# MCU.net
KiCad netlist of a schematic drawn in Altium Designer
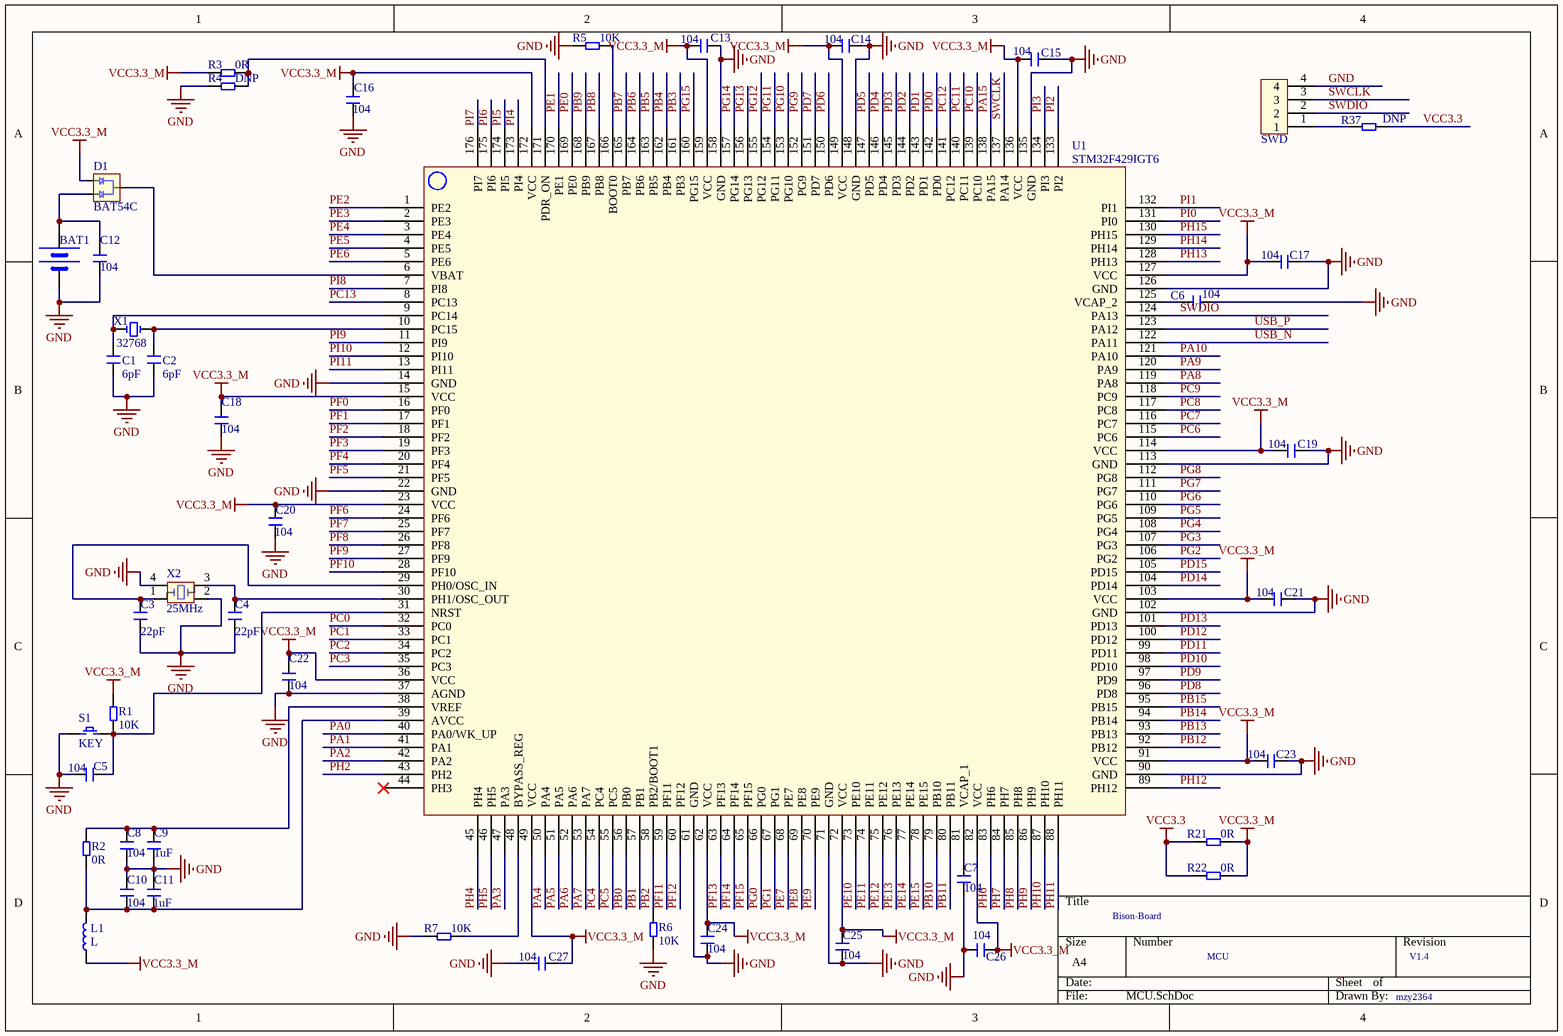
[diagram p0: MCU.SchDoc]

(export (version "E")
  (design (tool "Eeschema 10.0.6"))
  (components
    (comp (ref "BAT1")
      (value "BATTERY")
      (footprint "SBAT-1220")
      (libsource (lib "Bison-Board") (part "BATTERY"))
    )
    (comp (ref "C1") (value "6pF") (footprint "C 0603") (libsource (lib "Bison-Board") (part "CAP")))
    (comp (ref "C2")
      (value "6pF")
      (footprint "C 0603")
      (libsource (lib "altium-import") (part "root_1_CAP_"))
    )
    (comp (ref "C3") (value "22pF") (footprint "C 0603") (libsource (lib "Bison-Board") (part "CAP")))
    (comp (ref "C4") (value "22pF") (footprint "C 0603") (libsource (lib "Bison-Board") (part "CAP")))
    (comp (ref "C5") (value "104") (footprint "C 0603") (libsource (lib "Bison-Board") (part "CAP")))
    (comp (ref "C6") (value "104") (footprint "C 0603") (libsource (lib "Bison-Board") (part "CAP")))
    (comp (ref "C7") (value "104") (footprint "C 0603") (libsource (lib "Bison-Board") (part "CAP")))
    (comp (ref "C8") (value "104") (footprint "C 0603") (libsource (lib "Bison-Board") (part "CAP")))
    (comp (ref "C9") (value "1uF") (footprint "C 0603") (libsource (lib "Bison-Board") (part "CAP")))
    (comp (ref "C10") (value "104") (footprint "C 0603") (libsource (lib "Bison-Board") (part "CAP")))
    (comp (ref "C11") (value "1uF") (footprint "C 0603") (libsource (lib "Bison-Board") (part "CAP")))
    (comp (ref "C12") (value "104") (footprint "C 0603") (libsource (lib "Bison-Board") (part "CAP")))
    (comp (ref "C13") (value "104") (footprint "C 0603") (libsource (lib "Bison-Board") (part "CAP")))
    (comp (ref "C14") (value "104") (footprint "C 0603") (libsource (lib "Bison-Board") (part "CAP")))
    (comp (ref "C15") (value "104") (footprint "C 0603") (libsource (lib "Bison-Board") (part "CAP")))
    (comp (ref "C16") (value "104") (footprint "C 0603") (libsource (lib "Bison-Board") (part "CAP")))
    (comp (ref "C17") (value "104") (footprint "C 0603") (libsource (lib "Bison-Board") (part "CAP")))
    (comp (ref "C18") (value "104") (footprint "C 0603") (libsource (lib "Bison-Board") (part "CAP")))
    (comp (ref "C19") (value "104") (footprint "C 0603") (libsource (lib "Bison-Board") (part "CAP")))
    (comp (ref "C20") (value "104") (footprint "C 0603") (libsource (lib "Bison-Board") (part "CAP")))
    (comp (ref "C21") (value "104") (footprint "C 0603") (libsource (lib "Bison-Board") (part "CAP")))
    (comp (ref "C22") (value "104") (footprint "C 0603") (libsource (lib "Bison-Board") (part "CAP")))
    (comp (ref "C23") (value "104") (footprint "C 0603") (libsource (lib "Bison-Board") (part "CAP")))
    (comp (ref "C24") (value "104") (footprint "C 0603") (libsource (lib "Bison-Board") (part "CAP")))
    (comp (ref "C25") (value "104") (footprint "C 0603") (libsource (lib "Bison-Board") (part "CAP")))
    (comp (ref "C26") (value "104") (footprint "C 0603") (libsource (lib "Bison-Board") (part "CAP")))
    (comp (ref "C27") (value "104") (footprint "C 0603") (libsource (lib "Bison-Board") (part "CAP")))
    (comp (ref "D1") (value "BAT54C") (footprint "SOT23-3") (libsource (lib "Bison-Board") (part "BAT54C")))
    (comp (ref "L1") (value "L") (footprint "L 0603") (libsource (lib "Bison-Board") (part "L")))
    (comp (ref "R1") (value "10K") (footprint "R 0603") (libsource (lib "Bison-Board") (part "RES")))
    (comp (ref "R2") (value "0R") (footprint "R 0603") (libsource (lib "Bison-Board") (part "RES")))
    (comp (ref "R3") (value "0R") (footprint "R 0603") (libsource (lib "Bison-Board") (part "RES")))
    (comp (ref "R4") (value "DNP") (footprint "R 0603") (libsource (lib "Bison-Board") (part "RES")))
    (comp (ref "R5") (value "10K") (footprint "R 0603") (libsource (lib "Bison-Board") (part "RES")))
    (comp (ref "R6") (value "10K") (footprint "R 0603") (libsource (lib "Bison-Board") (part "RES")))
    (comp (ref "R7") (value "10K") (footprint "R 0603") (libsource (lib "Bison-Board") (part "RES")))
    (comp (ref "R21") (value "0R") (footprint "R 0603") (libsource (lib "Bison-Board") (part "RES")))
    (comp (ref "R22") (value "0R") (footprint "R 0603") (libsource (lib "Bison-Board") (part "RES")))
    (comp (ref "R37") (value "DNP") (footprint "R 0603") (libsource (lib "Bison-Board") (part "RES")))
    (comp (ref "S1")
      (value "KEY")
      (footprint "KEY SMD-3*6*2.5")
      (libsource (lib "squ-guiboard") (part "KEY"))
    )
    (comp (ref "SWD")
      (value "Header 4")
      (footprint "XH2.54-LS-4P")
      (libsource (lib "Bison-Board") (part "Header 4"))
    )
    (comp (ref "U1")
      (value "STM32F429IGT6")
      (footprint "STM32F429IG")
      (libsource (lib "Bison-Board") (part "STM32F429IGT6"))
    )
    (comp (ref "X1") (value "32768") (footprint "XTAL-3215") (libsource (lib "Bison-Board") (part "XTAL-2P")))
    (comp (ref "X2") (value "25MHz") (footprint "XTAL-3225") (libsource (lib "Bison-Board") (part "XTAL-4P")))
  )
  (nets
    (net (code "1") (name "/PA0") (class "Default")
      (node (ref "U1") (pin "40") (pinfunction "PA0/WK_UP_40") (pintype "passive"))
    )
    (net (code "2") (name "/PA1") (class "Default")
      (node (ref "U1") (pin "41") (pinfunction "PA1_41") (pintype "passive"))
    )
    (net (code "3") (name "/PA2") (class "Default")
      (node (ref "U1") (pin "42") (pinfunction "PA2_42") (pintype "passive"))
    )
    (net (code "4") (name "/PA3") (class "Default")
      (node (ref "U1") (pin "47") (pinfunction "PA3_47") (pintype "passive"))
    )
    (net (code "5") (name "/PA4") (class "Default")
      (node (ref "U1") (pin "50") (pinfunction "PA4_50") (pintype "passive"))
    )
    (net (code "6") (name "/PA5") (class "Default")
      (node (ref "U1") (pin "51") (pinfunction "PA5_51") (pintype "passive"))
    )
    (net (code "7") (name "/PA6") (class "Default")
      (node (ref "U1") (pin "52") (pinfunction "PA6_52") (pintype "passive"))
    )
    (net (code "8") (name "/PA7") (class "Default")
      (node (ref "U1") (pin "53") (pinfunction "PA7_53") (pintype "passive"))
    )
    (net (code "9") (name "/PA8") (class "Default")
      (node (ref "U1") (pin "119") (pinfunction "PA8_119") (pintype "passive"))
    )
    (net (code "10") (name "/PA9") (class "Default")
      (node (ref "U1") (pin "120") (pinfunction "PA9_120") (pintype "passive"))
    )
    (net (code "11") (name "/PA10") (class "Default")
      (node (ref "U1") (pin "121") (pinfunction "PA10_121") (pintype "passive"))
    )
    (net (code "12") (name "/PA15") (class "Default")
      (node (ref "U1") (pin "138") (pinfunction "PA15_138") (pintype "passive"))
    )
    (net (code "13") (name "/PB0") (class "Default")
      (node (ref "U1") (pin "56") (pinfunction "PB0_56") (pintype "passive"))
    )
    (net (code "14") (name "/PB1") (class "Default")
      (node (ref "U1") (pin "57") (pinfunction "PB1_57") (pintype "passive"))
    )
    (net (code "15") (name "/PB2") (class "Default")
      (node (ref "R6") (pin "2") (pintype "passive"))
      (node (ref "U1") (pin "58") (pinfunction "PB2/BOOT1_58") (pintype "passive"))
    )
    (net (code "16") (name "/PB3") (class "Default")
      (node (ref "U1") (pin "161") (pinfunction "PB3_161") (pintype "passive"))
    )
    (net (code "17") (name "/PB4") (class "Default")
      (node (ref "U1") (pin "162") (pinfunction "PB4_162") (pintype "passive"))
    )
    (net (code "18") (name "/PB5") (class "Default")
      (node (ref "U1") (pin "163") (pinfunction "PB5_163") (pintype "passive"))
    )
    (net (code "19") (name "/PB6") (class "Default")
      (node (ref "U1") (pin "164") (pinfunction "PB6_164") (pintype "passive"))
    )
    (net (code "20") (name "/PB7") (class "Default")
      (node (ref "U1") (pin "165") (pinfunction "PB7_165") (pintype "passive"))
    )
    (net (code "21") (name "/PB8") (class "Default")
      (node (ref "U1") (pin "167") (pinfunction "PB8_167") (pintype "passive"))
    )
    (net (code "22") (name "/PB9") (class "Default")
      (node (ref "U1") (pin "168") (pinfunction "PB9_168") (pintype "passive"))
    )
    (net (code "23") (name "/PB10") (class "Default")
      (node (ref "U1") (pin "79") (pinfunction "PB10_79") (pintype "passive"))
    )
    (net (code "24") (name "/PB11") (class "Default")
      (node (ref "U1") (pin "80") (pinfunction "PB11_80") (pintype "passive"))
    )
    (net (code "25") (name "/PB12") (class "Default")
      (node (ref "U1") (pin "92") (pinfunction "PB12_92") (pintype "passive"))
    )
    (net (code "26") (name "/PB13") (class "Default")
      (node (ref "U1") (pin "93") (pinfunction "PB13_93") (pintype "passive"))
    )
    (net (code "27") (name "/PB14") (class "Default")
      (node (ref "U1") (pin "94") (pinfunction "PB14_94") (pintype "passive"))
    )
    (net (code "28") (name "/PB15") (class "Default")
      (node (ref "U1") (pin "95") (pinfunction "PB15_95") (pintype "passive"))
    )
    (net (code "29") (name "/PC0") (class "Default")
      (node (ref "U1") (pin "32") (pinfunction "PC0_32") (pintype "passive"))
    )
    (net (code "30") (name "/PC1") (class "Default")
      (node (ref "U1") (pin "33") (pinfunction "PC1_33") (pintype "passive"))
    )
    (net (code "31") (name "/PC2") (class "Default")
      (node (ref "U1") (pin "34") (pinfunction "PC2_34") (pintype "passive"))
    )
    (net (code "32") (name "/PC3") (class "Default")
      (node (ref "U1") (pin "35") (pinfunction "PC3_35") (pintype "passive"))
    )
    (net (code "33") (name "/PC4") (class "Default")
      (node (ref "U1") (pin "54") (pinfunction "PC4_54") (pintype "passive"))
    )
    (net (code "34") (name "/PC5") (class "Default")
      (node (ref "U1") (pin "55") (pinfunction "PC5_55") (pintype "passive"))
    )
    (net (code "35") (name "/PC6") (class "Default")
      (node (ref "U1") (pin "115") (pinfunction "PC6_115") (pintype "passive"))
    )
    (net (code "36") (name "/PC7") (class "Default")
      (node (ref "U1") (pin "116") (pinfunction "PC7_116") (pintype "passive"))
    )
    (net (code "37") (name "/PC8") (class "Default")
      (node (ref "U1") (pin "117") (pinfunction "PC8_117") (pintype "passive"))
    )
    (net (code "38") (name "/PC9") (class "Default")
      (node (ref "U1") (pin "118") (pinfunction "PC9_118") (pintype "passive"))
    )
    (net (code "39") (name "/PC10") (class "Default")
      (node (ref "U1") (pin "139") (pinfunction "PC10_139") (pintype "passive"))
    )
    (net (code "40") (name "/PC11") (class "Default")
      (node (ref "U1") (pin "140") (pinfunction "PC11_140") (pintype "passive"))
    )
    (net (code "41") (name "/PC12") (class "Default")
      (node (ref "U1") (pin "141") (pinfunction "PC12_141") (pintype "passive"))
    )
    (net (code "42") (name "/PC13") (class "Default")
      (node (ref "U1") (pin "8") (pinfunction "PC13_8") (pintype "passive"))
    )
    (net (code "43") (name "/PD0") (class "Default")
      (node (ref "U1") (pin "142") (pinfunction "PD0_142") (pintype "passive"))
    )
    (net (code "44") (name "/PD1") (class "Default")
      (node (ref "U1") (pin "143") (pinfunction "PD1_143") (pintype "passive"))
    )
    (net (code "45") (name "/PD2") (class "Default")
      (node (ref "U1") (pin "144") (pinfunction "PD2_144") (pintype "passive"))
    )
    (net (code "46") (name "/PD3") (class "Default")
      (node (ref "U1") (pin "145") (pinfunction "PD3_145") (pintype "passive"))
    )
    (net (code "47") (name "/PD4") (class "Default")
      (node (ref "U1") (pin "146") (pinfunction "PD4_146") (pintype "passive"))
    )
    (net (code "48") (name "/PD5") (class "Default")
      (node (ref "U1") (pin "147") (pinfunction "PD5_147") (pintype "passive"))
    )
    (net (code "49") (name "/PD6") (class "Default")
      (node (ref "U1") (pin "150") (pinfunction "PD6_150") (pintype "passive"))
    )
    (net (code "50") (name "/PD7") (class "Default")
      (node (ref "U1") (pin "151") (pinfunction "PD7_151") (pintype "passive"))
    )
    (net (code "51") (name "/PD8") (class "Default")
      (node (ref "U1") (pin "96") (pinfunction "PD8_96") (pintype "passive"))
    )
    (net (code "52") (name "/PD9") (class "Default")
      (node (ref "U1") (pin "97") (pinfunction "PD9_97") (pintype "passive"))
    )
    (net (code "53") (name "/PD10") (class "Default")
      (node (ref "U1") (pin "98") (pinfunction "PD10_98") (pintype "passive"))
    )
    (net (code "54") (name "/PD11") (class "Default")
      (node (ref "U1") (pin "99") (pinfunction "PD11_99") (pintype "passive"))
    )
    (net (code "55") (name "/PD12") (class "Default")
      (node (ref "U1") (pin "100") (pinfunction "PD12_100") (pintype "passive"))
    )
    (net (code "56") (name "/PD13") (class "Default")
      (node (ref "U1") (pin "101") (pinfunction "PD13_101") (pintype "passive"))
    )
    (net (code "57") (name "/PD14") (class "Default")
      (node (ref "U1") (pin "104") (pinfunction "PD14_104") (pintype "passive"))
    )
    (net (code "58") (name "/PD15") (class "Default")
      (node (ref "U1") (pin "105") (pinfunction "PD15_105") (pintype "passive"))
    )
    (net (code "59") (name "/PE0") (class "Default")
      (node (ref "U1") (pin "169") (pinfunction "PE0_169") (pintype "passive"))
    )
    (net (code "60") (name "/PE1") (class "Default")
      (node (ref "U1") (pin "170") (pinfunction "PE1_170") (pintype "passive"))
    )
    (net (code "61") (name "/PE2") (class "Default")
      (node (ref "U1") (pin "1") (pinfunction "PE2_1") (pintype "passive"))
    )
    (net (code "62") (name "/PE3") (class "Default")
      (node (ref "U1") (pin "2") (pinfunction "PE3_2") (pintype "passive"))
    )
    (net (code "63") (name "/PE4") (class "Default")
      (node (ref "U1") (pin "3") (pinfunction "PE4_3") (pintype "passive"))
    )
    (net (code "64") (name "/PE5") (class "Default")
      (node (ref "U1") (pin "4") (pinfunction "PE5_4") (pintype "passive"))
    )
    (net (code "65") (name "/PE6") (class "Default")
      (node (ref "U1") (pin "5") (pinfunction "PE6_5") (pintype "passive"))
    )
    (net (code "66") (name "/PE7") (class "Default")
      (node (ref "U1") (pin "68") (pinfunction "PE7_68") (pintype "passive"))
    )
    (net (code "67") (name "/PE8") (class "Default")
      (node (ref "U1") (pin "69") (pinfunction "PE8_69") (pintype "passive"))
    )
    (net (code "68") (name "/PE9") (class "Default")
      (node (ref "U1") (pin "70") (pinfunction "PE9_70") (pintype "passive"))
    )
    (net (code "69") (name "/PE10") (class "Default")
      (node (ref "U1") (pin "73") (pinfunction "PE10_73") (pintype "passive"))
    )
    (net (code "70") (name "/PE11") (class "Default")
      (node (ref "U1") (pin "74") (pinfunction "PE11_74") (pintype "passive"))
    )
    (net (code "71") (name "/PE12") (class "Default")
      (node (ref "U1") (pin "75") (pinfunction "PE12_75") (pintype "passive"))
    )
    (net (code "72") (name "/PE13") (class "Default")
      (node (ref "U1") (pin "76") (pinfunction "PE13_76") (pintype "passive"))
    )
    (net (code "73") (name "/PE14") (class "Default")
      (node (ref "U1") (pin "77") (pinfunction "PE14_77") (pintype "passive"))
    )
    (net (code "74") (name "/PE15") (class "Default")
      (node (ref "U1") (pin "78") (pinfunction "PE15_78") (pintype "passive"))
    )
    (net (code "75") (name "/PF0") (class "Default")
      (node (ref "U1") (pin "16") (pinfunction "PF0_16") (pintype "passive"))
    )
    (net (code "76") (name "/PF1") (class "Default")
      (node (ref "U1") (pin "17") (pinfunction "PF1_17") (pintype "passive"))
    )
    (net (code "77") (name "/PF2") (class "Default")
      (node (ref "U1") (pin "18") (pinfunction "PF2_18") (pintype "passive"))
    )
    (net (code "78") (name "/PF3") (class "Default")
      (node (ref "U1") (pin "19") (pinfunction "PF3_19") (pintype "passive"))
    )
    (net (code "79") (name "/PF4") (class "Default")
      (node (ref "U1") (pin "20") (pinfunction "PF4_20") (pintype "passive"))
    )
    (net (code "80") (name "/PF5") (class "Default")
      (node (ref "U1") (pin "21") (pinfunction "PF5_21") (pintype "passive"))
    )
    (net (code "81") (name "/PF6") (class "Default")
      (node (ref "U1") (pin "24") (pinfunction "PF6_24") (pintype "passive"))
    )
    (net (code "82") (name "/PF7") (class "Default")
      (node (ref "U1") (pin "25") (pinfunction "PF7_25") (pintype "passive"))
    )
    (net (code "83") (name "/PF8") (class "Default")
      (node (ref "U1") (pin "26") (pinfunction "PF8_26") (pintype "passive"))
    )
    (net (code "84") (name "/PF9") (class "Default")
      (node (ref "U1") (pin "27") (pinfunction "PF9_27") (pintype "passive"))
    )
    (net (code "85") (name "/PF10") (class "Default")
      (node (ref "U1") (pin "28") (pinfunction "PF10_28") (pintype "passive"))
    )
    (net (code "86") (name "/PF11") (class "Default")
      (node (ref "U1") (pin "59") (pinfunction "PF11_59") (pintype "passive"))
    )
    (net (code "87") (name "/PF12") (class "Default")
      (node (ref "U1") (pin "60") (pinfunction "PF12_60") (pintype "passive"))
    )
    (net (code "88") (name "/PF13") (class "Default")
      (node (ref "U1") (pin "63") (pinfunction "PF13_63") (pintype "passive"))
    )
    (net (code "89") (name "/PF14") (class "Default")
      (node (ref "U1") (pin "64") (pinfunction "PF14_64") (pintype "passive"))
    )
    (net (code "90") (name "/PF15") (class "Default")
      (node (ref "U1") (pin "65") (pinfunction "PF15_65") (pintype "passive"))
    )
    (net (code "91") (name "/PG0") (class "Default")
      (node (ref "U1") (pin "66") (pinfunction "PG0_66") (pintype "passive"))
    )
    (net (code "92") (name "/PG1") (class "Default")
      (node (ref "U1") (pin "67") (pinfunction "PG1_67") (pintype "passive"))
    )
    (net (code "93") (name "/PG2") (class "Default")
      (node (ref "U1") (pin "106") (pinfunction "PG2_106") (pintype "passive"))
    )
    (net (code "94") (name "/PG3") (class "Default")
      (node (ref "U1") (pin "107") (pinfunction "PG3_107") (pintype "passive"))
    )
    (net (code "95") (name "/PG4") (class "Default")
      (node (ref "U1") (pin "108") (pinfunction "PG4_108") (pintype "passive"))
    )
    (net (code "96") (name "/PG5") (class "Default")
      (node (ref "U1") (pin "109") (pinfunction "PG5_109") (pintype "passive"))
    )
    (net (code "97") (name "/PG6") (class "Default")
      (node (ref "U1") (pin "110") (pinfunction "PG6_110") (pintype "passive"))
    )
    (net (code "98") (name "/PG7") (class "Default")
      (node (ref "U1") (pin "111") (pinfunction "PG7_111") (pintype "passive"))
    )
    (net (code "99") (name "/PG8") (class "Default")
      (node (ref "U1") (pin "112") (pinfunction "PG8_112") (pintype "passive"))
    )
    (net (code "100") (name "/PG9") (class "Default")
      (node (ref "U1") (pin "152") (pinfunction "PG9_152") (pintype "passive"))
    )
    (net (code "101") (name "/PG10") (class "Default")
      (node (ref "U1") (pin "153") (pinfunction "PG10_153") (pintype "passive"))
    )
    (net (code "102") (name "/PG11") (class "Default")
      (node (ref "U1") (pin "154") (pinfunction "PG11_154") (pintype "passive"))
    )
    (net (code "103") (name "/PG12") (class "Default")
      (node (ref "U1") (pin "155") (pinfunction "PG12_155") (pintype "passive"))
    )
    (net (code "104") (name "/PG13") (class "Default")
      (node (ref "U1") (pin "156") (pinfunction "PG13_156") (pintype "passive"))
    )
    (net (code "105") (name "/PG14") (class "Default")
      (node (ref "U1") (pin "157") (pinfunction "PG14_157") (pintype "passive"))
    )
    (net (code "106") (name "/PG15") (class "Default")
      (node (ref "U1") (pin "160") (pinfunction "PG15_160") (pintype "passive"))
    )
    (net (code "107") (name "/PH2") (class "Default")
      (node (ref "U1") (pin "43") (pinfunction "PH2_43") (pintype "passive"))
    )
    (net (code "108") (name "/PH4") (class "Default")
      (node (ref "U1") (pin "45") (pinfunction "PH4_45") (pintype "passive"))
    )
    (net (code "109") (name "/PH5") (class "Default")
      (node (ref "U1") (pin "46") (pinfunction "PH5_46") (pintype "passive"))
    )
    (net (code "110") (name "/PH6") (class "Default")
      (node (ref "U1") (pin "83") (pinfunction "PH6_83") (pintype "passive"))
    )
    (net (code "111") (name "/PH7") (class "Default")
      (node (ref "U1") (pin "84") (pinfunction "PH7_84") (pintype "passive"))
    )
    (net (code "112") (name "/PH8") (class "Default")
      (node (ref "U1") (pin "85") (pinfunction "PH8_85") (pintype "passive"))
    )
    (net (code "113") (name "/PH9") (class "Default")
      (node (ref "U1") (pin "86") (pinfunction "PH9_86") (pintype "passive"))
    )
    (net (code "114") (name "/PH10") (class "Default")
      (node (ref "U1") (pin "87") (pinfunction "PH10_87") (pintype "passive"))
    )
    (net (code "115") (name "/PH11") (class "Default")
      (node (ref "U1") (pin "88") (pinfunction "PH11_88") (pintype "passive"))
    )
    (net (code "116") (name "/PH12") (class "Default")
      (node (ref "U1") (pin "89") (pinfunction "PH12_89") (pintype "passive"))
    )
    (net (code "117") (name "/PH13") (class "Default")
      (node (ref "U1") (pin "128") (pinfunction "PH13_128") (pintype "passive"))
    )
    (net (code "118") (name "/PH14") (class "Default")
      (node (ref "U1") (pin "129") (pinfunction "PH14_129") (pintype "passive"))
    )
    (net (code "119") (name "/PH15") (class "Default")
      (node (ref "U1") (pin "130") (pinfunction "PH15_130") (pintype "passive"))
    )
    (net (code "120") (name "/PI0") (class "Default")
      (node (ref "U1") (pin "131") (pinfunction "PI0_131") (pintype "passive"))
    )
    (net (code "121") (name "/PI1") (class "Default")
      (node (ref "U1") (pin "132") (pinfunction "PI1_132") (pintype "passive"))
    )
    (net (code "122") (name "/PI2") (class "Default")
      (node (ref "U1") (pin "133") (pinfunction "PI2_133") (pintype "passive"))
    )
    (net (code "123") (name "/PI3") (class "Default")
      (node (ref "U1") (pin "134") (pinfunction "PI3_134") (pintype "passive"))
    )
    (net (code "124") (name "/PI4") (class "Default")
      (node (ref "U1") (pin "173") (pinfunction "PI4_173") (pintype "passive"))
    )
    (net (code "125") (name "/PI5") (class "Default")
      (node (ref "U1") (pin "174") (pinfunction "PI5_174") (pintype "passive"))
    )
    (net (code "126") (name "/PI6") (class "Default")
      (node (ref "U1") (pin "175") (pinfunction "PI6_175") (pintype "passive"))
    )
    (net (code "127") (name "/PI7") (class "Default")
      (node (ref "U1") (pin "176") (pinfunction "PI7_176") (pintype "passive"))
    )
    (net (code "128") (name "/PI8") (class "Default")
      (node (ref "U1") (pin "7") (pinfunction "PI8_7") (pintype "passive"))
    )
    (net (code "129") (name "/PI9") (class "Default")
      (node (ref "U1") (pin "11") (pinfunction "PI9_11") (pintype "passive"))
    )
    (net (code "130") (name "/PI10") (class "Default")
      (node (ref "U1") (pin "12") (pinfunction "PI10_12") (pintype "passive"))
    )
    (net (code "131") (name "/PI11") (class "Default")
      (node (ref "U1") (pin "13") (pinfunction "PI11_13") (pintype "passive"))
    )
    (net (code "132") (name "/SWCLK") (class "Default")
      (node (ref "SWD") (pin "3") (pinfunction "3_3") (pintype "passive"))
      (node (ref "U1") (pin "137") (pinfunction "PA14_137") (pintype "passive"))
    )
    (net (code "133") (name "/SWDIO") (class "Default")
      (node (ref "SWD") (pin "2") (pinfunction "2_2") (pintype "passive"))
      (node (ref "U1") (pin "124") (pinfunction "PA13_124") (pintype "passive"))
    )
    (net (code "134") (name "/USB_N") (class "Default")
      (node (ref "U1") (pin "122") (pinfunction "PA11_122") (pintype "passive"))
    )
    (net (code "135") (name "/USB_P") (class "Default")
      (node (ref "U1") (pin "123") (pinfunction "PA12_123") (pintype "passive"))
    )
    (net (code "136") (name "GND") (class "Default")
      (node (ref "BAT1") (pin "2") (pinfunction "GND_2") (pintype "passive"))
      (node (ref "C1") (pin "1") (pinfunction "1_1") (pintype "passive"))
      (node (ref "C10") (pin "2") (pinfunction "2_2") (pintype "passive"))
      (node (ref "C11") (pin "2") (pinfunction "2_2") (pintype "passive"))
      (node (ref "C12") (pin "2") (pinfunction "2_2") (pintype "passive"))
      (node (ref "C13") (pin "1") (pinfunction "1_1") (pintype "passive"))
      (node (ref "C14") (pin "1") (pinfunction "1_1") (pintype "passive"))
      (node (ref "C15") (pin "1") (pinfunction "1_1") (pintype "passive"))
      (node (ref "C16") (pin "2") (pinfunction "2_2") (pintype "passive"))
      (node (ref "C17") (pin "1") (pinfunction "1_1") (pintype "passive"))
      (node (ref "C18") (pin "1") (pinfunction "1_1") (pintype "passive"))
      (node (ref "C19") (pin "1") (pinfunction "1_1") (pintype "passive"))
      (node (ref "C2") (pin "1") (pinfunction "1_1") (pintype "passive"))
      (node (ref "C20") (pin "1") (pinfunction "1_1") (pintype "passive"))
      (node (ref "C21") (pin "1") (pinfunction "1_1") (pintype "passive"))
      (node (ref "C22") (pin "1") (pinfunction "1_1") (pintype "passive"))
      (node (ref "C23") (pin "1") (pinfunction "1_1") (pintype "passive"))
      (node (ref "C24") (pin "1") (pinfunction "1_1") (pintype "passive"))
      (node (ref "C25") (pin "1") (pinfunction "1_1") (pintype "passive"))
      (node (ref "C26") (pin "2") (pinfunction "2_2") (pintype "passive"))
      (node (ref "C27") (pin "2") (pinfunction "2_2") (pintype "passive"))
      (node (ref "C3") (pin "1") (pinfunction "1_1") (pintype "passive"))
      (node (ref "C4") (pin "1") (pinfunction "1_1") (pintype "passive"))
      (node (ref "C5") (pin "2") (pinfunction "2_2") (pintype "passive"))
      (node (ref "C6") (pin "2") (pinfunction "2_2") (pintype "passive"))
      (node (ref "C7") (pin "1") (pinfunction "1_1") (pintype "passive"))
      (node (ref "C8") (pin "1") (pinfunction "1_1") (pintype "passive"))
      (node (ref "C9") (pin "1") (pinfunction "1_1") (pintype "passive"))
      (node (ref "R4") (pin "2") (pintype "passive"))
      (node (ref "R5") (pin "2") (pintype "passive"))
      (node (ref "R6") (pin "1") (pintype "passive"))
      (node (ref "R7") (pin "2") (pintype "passive"))
      (node (ref "S1") (pin "1") (pinfunction "1_1") (pintype "passive"))
      (node (ref "SWD") (pin "4") (pinfunction "4_4") (pintype "passive"))
      (node (ref "U1") (pin "102") (pinfunction "GND_102") (pintype "passive"))
      (node (ref "U1") (pin "113") (pinfunction "GND_113") (pintype "passive"))
      (node (ref "U1") (pin "126") (pinfunction "GND_126") (pintype "passive"))
      (node (ref "U1") (pin "135") (pinfunction "GND_135") (pintype "passive"))
      (node (ref "U1") (pin "14") (pinfunction "GND_14") (pintype "passive"))
      (node (ref "U1") (pin "148") (pinfunction "GND_148") (pintype "passive"))
      (node (ref "U1") (pin "158") (pinfunction "GND_158") (pintype "passive"))
      (node (ref "U1") (pin "22") (pinfunction "GND_22") (pintype "passive"))
      (node (ref "U1") (pin "37") (pinfunction "AGND_37") (pintype "passive"))
      (node (ref "U1") (pin "61") (pinfunction "GND_61") (pintype "passive"))
      (node (ref "U1") (pin "71") (pinfunction "GND_71") (pintype "passive"))
      (node (ref "U1") (pin "90") (pinfunction "GND_90") (pintype "passive"))
      (node (ref "X2") (pin "2") (pinfunction "2_2") (pintype "passive"))
      (node (ref "X2") (pin "4") (pinfunction "4_4") (pintype "passive"))
    )
    (net (code "137") (name "Net-(BAT1-VCC)") (class "Default")
      (node (ref "BAT1") (pin "1") (pinfunction "VCC_1") (pintype "passive"))
      (node (ref "C12") (pin "1") (pinfunction "1_1") (pintype "passive"))
      (node (ref "D1") (pin "2") (pinfunction "2_2") (pintype "passive"))
    )
    (net (code "138") (name "Net-(R37-Pad1)") (class "Default")
      (node (ref "R37") (pin "1") (pintype "passive"))
      (node (ref "SWD") (pin "1") (pinfunction "1_1") (pintype "passive"))
    )
    (net (code "139") (name "Net-(U1-AVCC)") (class "Default")
      (node (ref "C10") (pin "1") (pinfunction "1_1") (pintype "passive"))
      (node (ref "C11") (pin "1") (pinfunction "1_1") (pintype "passive"))
      (node (ref "L1") (pin "1") (pinfunction "1_1") (pintype "passive"))
      (node (ref "R2") (pin "1") (pintype "passive"))
      (node (ref "U1") (pin "39") (pinfunction "AVCC_39") (pintype "passive"))
    )
    (net (code "140") (name "Net-(U1-BOOT0)") (class "Default")
      (node (ref "R5") (pin "1") (pintype "passive"))
      (node (ref "U1") (pin "166") (pinfunction "BOOT0_166") (pintype "passive"))
    )
    (net (code "141") (name "Net-(U1-BYPASS_REG)") (class "Default")
      (node (ref "R7") (pin "1") (pintype "passive"))
      (node (ref "U1") (pin "48") (pinfunction "BYPASS_REG_48") (pintype "passive"))
    )
    (net (code "142") (name "Net-(U1-NRST)") (class "Default")
      (node (ref "C5") (pin "1") (pinfunction "1_1") (pintype "passive"))
      (node (ref "R1") (pin "1") (pintype "passive"))
      (node (ref "S1") (pin "2") (pinfunction "2_2") (pintype "passive"))
      (node (ref "U1") (pin "31") (pinfunction "NRST_31") (pintype "passive"))
    )
    (net (code "143") (name "Net-(U1-PC14)") (class "Default")
      (node (ref "C1") (pin "2") (pinfunction "2_2") (pintype "passive"))
      (node (ref "U1") (pin "9") (pinfunction "PC14_9") (pintype "passive"))
      (node (ref "X1") (pin "1") (pinfunction "1_1") (pintype "passive"))
    )
    (net (code "144") (name "Net-(U1-PC15)") (class "Default")
      (node (ref "C2") (pin "2") (pinfunction "2_2") (pintype "passive"))
      (node (ref "U1") (pin "10") (pinfunction "PC15_10") (pintype "passive"))
      (node (ref "X1") (pin "2") (pinfunction "2_2") (pintype "passive"))
    )
    (net (code "145") (name "Net-(U1-PDR_ON)") (class "Default")
      (node (ref "R3") (pin "1") (pintype "passive"))
      (node (ref "R4") (pin "1") (pintype "passive"))
      (node (ref "U1") (pin "171") (pinfunction "PDR_ON_171") (pintype "passive"))
    )
    (net (code "146") (name "Net-(U1-PH0{slash}OSC_IN)") (class "Default")
      (node (ref "C3") (pin "2") (pinfunction "2_2") (pintype "passive"))
      (node (ref "U1") (pin "29") (pinfunction "PH0/OSC_IN_29") (pintype "passive"))
      (node (ref "X2") (pin "1") (pinfunction "1_1") (pintype "passive"))
    )
    (net (code "147") (name "Net-(U1-PH1{slash}OSC_OUT)") (class "Default")
      (node (ref "C4") (pin "2") (pinfunction "2_2") (pintype "passive"))
      (node (ref "U1") (pin "30") (pinfunction "PH1/OSC_OUT_30") (pintype "passive"))
      (node (ref "X2") (pin "3") (pinfunction "3_3") (pintype "passive"))
    )
    (net (code "148") (name "Net-(U1-VBAT)") (class "Default")
      (node (ref "D1") (pin "3") (pinfunction "3_3") (pintype "passive"))
      (node (ref "U1") (pin "6") (pinfunction "VBAT_6") (pintype "passive"))
    )
    (net (code "149") (name "Net-(U1-VCAP_1)") (class "Default")
      (node (ref "C7") (pin "2") (pinfunction "2_2") (pintype "passive"))
      (node (ref "U1") (pin "81") (pinfunction "VCAP_1_81") (pintype "passive"))
    )
    (net (code "150") (name "Net-(U1-VCAP_2)") (class "Default")
      (node (ref "C6") (pin "1") (pinfunction "1_1") (pintype "passive"))
      (node (ref "U1") (pin "125") (pinfunction "VCAP_2_125") (pintype "passive"))
    )
    (net (code "151") (name "Net-(U1-VREF)") (class "Default")
      (node (ref "C8") (pin "2") (pinfunction "2_2") (pintype "passive"))
      (node (ref "C9") (pin "2") (pinfunction "2_2") (pintype "passive"))
      (node (ref "R2") (pin "2") (pintype "passive"))
      (node (ref "U1") (pin "38") (pinfunction "VREF_38") (pintype "passive"))
    )
    (net (code "152") (name "VCC3.3") (class "Default")
      (node (ref "R21") (pin "1") (pintype "passive"))
      (node (ref "R22") (pin "1") (pintype "passive"))
      (node (ref "R37") (pin "2") (pintype "passive"))
    )
    (net (code "153") (name "VCC3.3_M") (class "Default")
      (node (ref "C13") (pin "2") (pinfunction "2_2") (pintype "passive"))
      (node (ref "C14") (pin "2") (pinfunction "2_2") (pintype "passive"))
      (node (ref "C15") (pin "2") (pinfunction "2_2") (pintype "passive"))
      (node (ref "C16") (pin "1") (pinfunction "1_1") (pintype "passive"))
      (node (ref "C17") (pin "2") (pinfunction "2_2") (pintype "passive"))
      (node (ref "C18") (pin "2") (pinfunction "2_2") (pintype "passive"))
      (node (ref "C19") (pin "2") (pinfunction "2_2") (pintype "passive"))
      (node (ref "C20") (pin "2") (pinfunction "2_2") (pintype "passive"))
      (node (ref "C21") (pin "2") (pinfunction "2_2") (pintype "passive"))
      (node (ref "C22") (pin "2") (pinfunction "2_2") (pintype "passive"))
      (node (ref "C23") (pin "2") (pinfunction "2_2") (pintype "passive"))
      (node (ref "C24") (pin "2") (pinfunction "2_2") (pintype "passive"))
      (node (ref "C25") (pin "2") (pinfunction "2_2") (pintype "passive"))
      (node (ref "C26") (pin "1") (pinfunction "1_1") (pintype "passive"))
      (node (ref "C27") (pin "1") (pinfunction "1_1") (pintype "passive"))
      (node (ref "D1") (pin "1") (pinfunction "1_1") (pintype "passive"))
      (node (ref "L1") (pin "2") (pinfunction "2_2") (pintype "passive"))
      (node (ref "R1") (pin "2") (pintype "passive"))
      (node (ref "R21") (pin "2") (pintype "passive"))
      (node (ref "R22") (pin "2") (pintype "passive"))
      (node (ref "R3") (pin "2") (pintype "passive"))
      (node (ref "U1") (pin "103") (pinfunction "VCC_103") (pintype "passive"))
      (node (ref "U1") (pin "114") (pinfunction "VCC_114") (pintype "passive"))
      (node (ref "U1") (pin "127") (pinfunction "VCC_127") (pintype "passive"))
      (node (ref "U1") (pin "136") (pinfunction "VCC_136") (pintype "passive"))
      (node (ref "U1") (pin "149") (pinfunction "VCC_149") (pintype "passive"))
      (node (ref "U1") (pin "15") (pinfunction "VCC_15") (pintype "passive"))
      (node (ref "U1") (pin "159") (pinfunction "VCC_159") (pintype "passive"))
      (node (ref "U1") (pin "172") (pinfunction "VCC_172") (pintype "passive"))
      (node (ref "U1") (pin "23") (pinfunction "VCC_23") (pintype "passive"))
      (node (ref "U1") (pin "36") (pinfunction "VCC_36") (pintype "passive"))
      (node (ref "U1") (pin "49") (pinfunction "VCC_49") (pintype "passive"))
      (node (ref "U1") (pin "62") (pinfunction "VCC_62") (pintype "passive"))
      (node (ref "U1") (pin "72") (pinfunction "VCC_72") (pintype "passive"))
      (node (ref "U1") (pin "82") (pinfunction "VCC_82") (pintype "passive"))
      (node (ref "U1") (pin "91") (pinfunction "VCC_91") (pintype "passive"))
    )
    (net (code "154") (name "unconnected-(U1-PH3-Pad44)") (class "Default")
      (node (ref "U1") (pin "44") (pinfunction "PH3_44") (pintype "passive+no_connect"))
    )
  )
)
